# Mosfet_Driver.net
KiCad netlist of a schematic drawn in Altium Designer
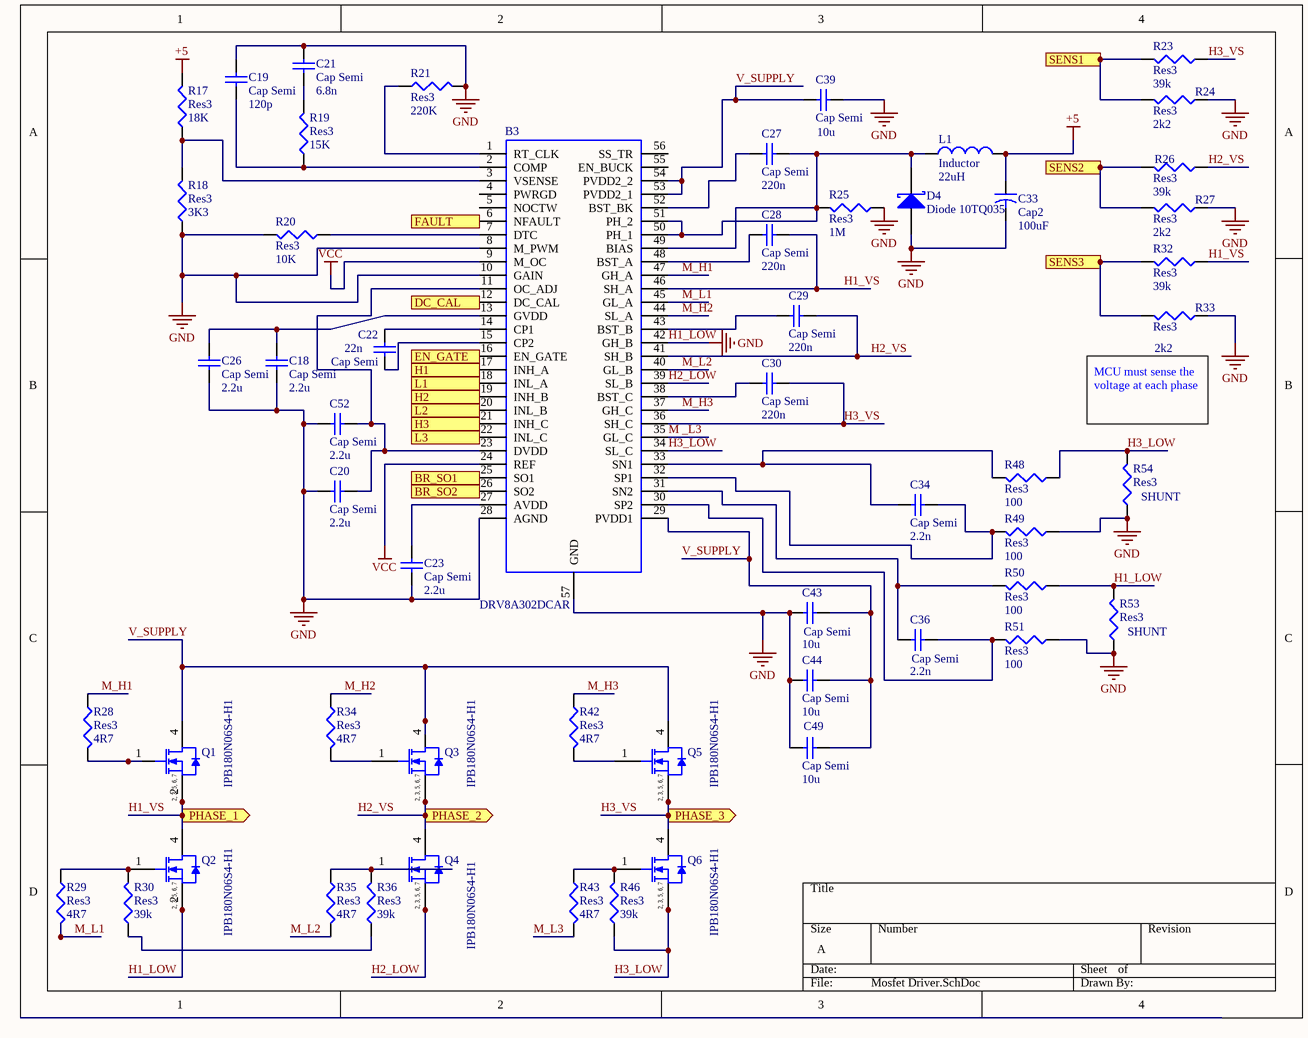
[diagram p0: Mosfet Driver.SchDoc]

(export (version "E")
  (design (tool "Eeschema 10.0.6"))
  (components
    (comp (ref "B3")
      (value "DRV8A302DCAR")
      (footprint "SOP50P810X120-57N")
      (description "3-Phase Brushless Motor Pre-Driver with Dual Current Sense Amps and Buck Converter (PWM Ctrl)")
      (fields (field (name "MANUFACTURER_PART_NUMBER") "DRV8302DCAR"))
      (libsource (lib "DRV8302DCAR") (part "DRV8302DCAR"))
    )
    (comp (ref "C18")
      (value "Cap Semi")
      (footprint "1608[0603]")
      (description "Capacitor (Semiconductor SIM Model)")
      (fields (field (name "ALTIUM_VALUE") "2.2u") (field (name "PUBLISHER") "Altium Limited"))
      (libsource (lib "Miscellaneous Devices") (part "Cap Semi"))
    )
    (comp (ref "C19")
      (value "Cap Semi")
      (footprint "1608[0603]")
      (description "Capacitor (Semiconductor SIM Model)")
      (fields (field (name "ALTIUM_VALUE") "120p") (field (name "PUBLISHER") "Altium Limited"))
      (libsource (lib "Miscellaneous Devices") (part "Cap Semi"))
    )
    (comp (ref "C20")
      (value "Cap Semi")
      (footprint "1608[0603]")
      (description "Capacitor (Semiconductor SIM Model)")
      (fields (field (name "ALTIUM_VALUE") "2.2u") (field (name "PUBLISHER") "Altium Limited"))
      (libsource (lib "Miscellaneous Devices") (part "Cap Semi"))
    )
    (comp (ref "C21")
      (value "Cap Semi")
      (footprint "1608[0603]")
      (description "Capacitor (Semiconductor SIM Model)")
      (fields (field (name "ALTIUM_VALUE") "6.8n") (field (name "PUBLISHER") "Altium Limited"))
      (libsource (lib "Miscellaneous Devices") (part "Cap Semi"))
    )
    (comp (ref "C22")
      (value "Cap Semi")
      (footprint "1608[0603]")
      (description "Capacitor (Semiconductor SIM Model)")
      (fields (field (name "ALTIUM_VALUE") "22n") (field (name "PUBLISHER") "Altium Limited"))
      (libsource (lib "Miscellaneous Devices") (part "Cap Semi"))
    )
    (comp (ref "C23")
      (value "Cap Semi")
      (footprint "1608[0603]")
      (description "Capacitor (Semiconductor SIM Model)")
      (fields (field (name "ALTIUM_VALUE") "2.2u") (field (name "PUBLISHER") "Altium Limited"))
      (libsource (lib "Miscellaneous Devices") (part "Cap Semi"))
    )
    (comp (ref "C26")
      (value "Cap Semi")
      (footprint "1608[0603]")
      (description "Capacitor (Semiconductor SIM Model)")
      (fields (field (name "ALTIUM_VALUE") "2.2u") (field (name "PUBLISHER") "Altium Limited"))
      (libsource (lib "Miscellaneous Devices") (part "Cap Semi"))
    )
    (comp (ref "C27")
      (value "Cap Semi")
      (footprint "1608[0603]")
      (description "Capacitor (Semiconductor SIM Model)")
      (fields (field (name "ALTIUM_VALUE") "220n") (field (name "PUBLISHER") "Altium Limited"))
      (libsource (lib "Miscellaneous Devices") (part "Cap Semi"))
    )
    (comp (ref "C28")
      (value "Cap Semi")
      (footprint "1608[0603]")
      (description "Capacitor (Semiconductor SIM Model)")
      (fields (field (name "ALTIUM_VALUE") "220n") (field (name "PUBLISHER") "Altium Limited"))
      (libsource (lib "Miscellaneous Devices") (part "Cap Semi"))
    )
    (comp (ref "C29")
      (value "Cap Semi")
      (footprint "1608[0603]")
      (description "Capacitor (Semiconductor SIM Model)")
      (fields (field (name "ALTIUM_VALUE") "220n") (field (name "PUBLISHER") "Altium Limited"))
      (libsource (lib "Miscellaneous Devices") (part "Cap Semi"))
    )
    (comp (ref "C30")
      (value "Cap Semi")
      (footprint "1608[0603]")
      (description "Capacitor (Semiconductor SIM Model)")
      (fields (field (name "ALTIUM_VALUE") "220n") (field (name "PUBLISHER") "Altium Limited"))
      (libsource (lib "Miscellaneous Devices") (part "Cap Semi"))
    )
    (comp (ref "C33")
      (value "Cap2")
      (footprint "CAPR5-4X5")
      (description "Capacitor")
      (fields (field (name "ALTIUM_VALUE") "100uF") (field (name "PUBLISHER") "Altium Limited"))
      (libsource (lib "Miscellaneous Devices") (part "Cap2"))
    )
    (comp (ref "C34")
      (value "Cap Semi")
      (footprint "1608[0603]")
      (description "Capacitor (Semiconductor SIM Model)")
      (fields (field (name "ALTIUM_VALUE") "2.2n") (field (name "PUBLISHER") "Altium Limited"))
      (libsource (lib "Miscellaneous Devices") (part "Cap Semi"))
    )
    (comp (ref "C36")
      (value "Cap Semi")
      (footprint "1608[0603]")
      (description "Capacitor (Semiconductor SIM Model)")
      (fields (field (name "ALTIUM_VALUE") "2.2n") (field (name "PUBLISHER") "Altium Limited"))
      (libsource (lib "Miscellaneous Devices") (part "Cap Semi"))
    )
    (comp (ref "C39")
      (value "Cap Semi")
      (footprint "1608[0603]")
      (description "Capacitor (Semiconductor SIM Model)")
      (fields (field (name "ALTIUM_VALUE") "10u") (field (name "PUBLISHER") "Altium Limited"))
      (libsource (lib "Miscellaneous Devices") (part "Cap Semi"))
    )
    (comp (ref "C43")
      (value "Cap Semi")
      (footprint "1608[0603]")
      (description "Capacitor (Semiconductor SIM Model)")
      (fields (field (name "ALTIUM_VALUE") "10u") (field (name "PUBLISHER") "Altium Limited"))
      (libsource (lib "Miscellaneous Devices") (part "Cap Semi"))
    )
    (comp (ref "C44")
      (value "Cap Semi")
      (footprint "1608[0603]")
      (description "Capacitor (Semiconductor SIM Model)")
      (fields (field (name "ALTIUM_VALUE") "10u") (field (name "PUBLISHER") "Altium Limited"))
      (libsource (lib "Miscellaneous Devices") (part "Cap Semi"))
    )
    (comp (ref "C49")
      (value "Cap Semi")
      (footprint "1608[0603]")
      (description "Capacitor (Semiconductor SIM Model)")
      (fields (field (name "ALTIUM_VALUE") "10u") (field (name "PUBLISHER") "Altium Limited"))
      (libsource (lib "Miscellaneous Devices") (part "Cap Semi"))
    )
    (comp (ref "C52")
      (value "Cap Semi")
      (footprint "1608[0603]")
      (description "Capacitor (Semiconductor SIM Model)")
      (fields (field (name "ALTIUM_VALUE") "2.2u") (field (name "PUBLISHER") "Altium Limited"))
      (libsource (lib "Miscellaneous Devices") (part "Cap Semi"))
    )
    (comp (ref "D4")
      (value "Diode 10TQ035")
      (footprint "TO-220AC")
      (description "Schottky Rectifier")
      (fields (field (name "PUBLISHER") "Altium Limited"))
      (libsource (lib "Miscellaneous Devices") (part "Diode 10TQ035"))
    )
    (comp (ref "L1")
      (value "Inductor")
      (footprint "0402-A")
      (fields (field (name "ALTIUM_VALUE") "22uH") (field (name "PUBLISHER") "Altium Limited"))
      (libsource (lib "Miscellaneous Devices") (part "Inductor"))
    )
    (comp (ref "Q1")
      (value "IPB180N06S4-H1")
      (footprint "INF-PG-TO263-7-3_N")
      (description "OptiMOS-T2 Power-Transistor, 60 V VDS, 180 A ID, PG-TO263-7-3, Reel, Green")
      (fields (field (name "MANUFACTURER") "Infineon"))
      (libsource (lib "Infineon_Power_MOSFET") (part "IPB180N06S4-H1"))
    )
    (comp (ref "Q2")
      (value "IPB180N06S4-H1")
      (footprint "INF-PG-TO263-7-3_N")
      (description "OptiMOS-T2 Power-Transistor, 60 V VDS, 180 A ID, PG-TO263-7-3, Reel, Green")
      (fields (field (name "MANUFACTURER") "Infineon"))
      (libsource (lib "Infineon_Power_MOSFET") (part "IPB180N06S4-H1"))
    )
    (comp (ref "Q3")
      (value "IPB180N06S4-H1")
      (footprint "INF-PG-TO263-7-3_N")
      (description "OptiMOS-T2 Power-Transistor, 60 V VDS, 180 A ID, PG-TO263-7-3, Reel, Green")
      (fields (field (name "MANUFACTURER") "Infineon"))
      (libsource (lib "Infineon_Power_MOSFET") (part "IPB180N06S4-H1"))
    )
    (comp (ref "Q4")
      (value "IPB180N06S4-H1")
      (footprint "INF-PG-TO263-7-3_N")
      (description "OptiMOS-T2 Power-Transistor, 60 V VDS, 180 A ID, PG-TO263-7-3, Reel, Green")
      (fields (field (name "MANUFACTURER") "Infineon"))
      (libsource (lib "Infineon_Power_MOSFET") (part "IPB180N06S4-H1"))
    )
    (comp (ref "Q5")
      (value "IPB180N06S4-H1")
      (footprint "INF-PG-TO263-7-3_N")
      (description "OptiMOS-T2 Power-Transistor, 60 V VDS, 180 A ID, PG-TO263-7-3, Reel, Green")
      (fields (field (name "MANUFACTURER") "Infineon"))
      (libsource (lib "Infineon_Power_MOSFET") (part "IPB180N06S4-H1"))
    )
    (comp (ref "Q6")
      (value "IPB180N06S4-H1")
      (footprint "INF-PG-TO263-7-3_N")
      (description "OptiMOS-T2 Power-Transistor, 60 V VDS, 180 A ID, PG-TO263-7-3, Reel, Green")
      (fields (field (name "MANUFACTURER") "Infineon"))
      (libsource (lib "Infineon_Power_MOSFET") (part "IPB180N06S4-H1"))
    )
    (comp (ref "R17")
      (value "Res3")
      (footprint "J1-0603")
      (description "Resistor")
      (fields (field (name "ALTIUM_VALUE") "18K") (field (name "PUBLISHER") "Altium Limited"))
      (libsource (lib "Miscellaneous Devices") (part "Res3"))
    )
    (comp (ref "R18")
      (value "Res3")
      (footprint "J1-0603")
      (description "Resistor")
      (fields (field (name "ALTIUM_VALUE") "3K3") (field (name "PUBLISHER") "Altium Limited"))
      (libsource (lib "Miscellaneous Devices") (part "Res3"))
    )
    (comp (ref "R19")
      (value "Res3")
      (footprint "J1-0603")
      (description "Resistor")
      (fields (field (name "ALTIUM_VALUE") "15K") (field (name "PUBLISHER") "Altium Limited"))
      (libsource (lib "Miscellaneous Devices") (part "Res3"))
    )
    (comp (ref "R20")
      (value "Res3")
      (footprint "J1-0603")
      (description "Resistor")
      (fields (field (name "ALTIUM_VALUE") "10K") (field (name "PUBLISHER") "Altium Limited"))
      (libsource (lib "Miscellaneous Devices") (part "Res3"))
    )
    (comp (ref "R21")
      (value "Res3")
      (footprint "J1-0603")
      (description "Resistor")
      (fields (field (name "ALTIUM_VALUE") "220K") (field (name "PUBLISHER") "Altium Limited"))
      (libsource (lib "Miscellaneous Devices") (part "Res3"))
    )
    (comp (ref "R23")
      (value "Res3")
      (footprint "J1-0603")
      (description "Resistor")
      (fields (field (name "ALTIUM_VALUE") "39k") (field (name "PUBLISHER") "Altium Limited"))
      (libsource (lib "Miscellaneous Devices") (part "Res3"))
    )
    (comp (ref "R24")
      (value "Res3")
      (footprint "J1-0603")
      (description "Resistor")
      (fields (field (name "ALTIUM_VALUE") "2k2") (field (name "PUBLISHER") "Altium Limited"))
      (libsource (lib "Miscellaneous Devices") (part "Res3"))
    )
    (comp (ref "R25")
      (value "Res3")
      (footprint "J1-0603")
      (description "Resistor")
      (fields (field (name "ALTIUM_VALUE") "1M") (field (name "PUBLISHER") "Altium Limited"))
      (libsource (lib "Miscellaneous Devices") (part "Res3"))
    )
    (comp (ref "R26")
      (value "Res3")
      (footprint "J1-0603")
      (description "Resistor")
      (fields (field (name "ALTIUM_VALUE") "39k") (field (name "PUBLISHER") "Altium Limited"))
      (libsource (lib "Miscellaneous Devices") (part "Res3"))
    )
    (comp (ref "R27")
      (value "Res3")
      (footprint "J1-0603")
      (description "Resistor")
      (fields (field (name "ALTIUM_VALUE") "2k2") (field (name "PUBLISHER") "Altium Limited"))
      (libsource (lib "Miscellaneous Devices") (part "Res3"))
    )
    (comp (ref "R28")
      (value "Res3")
      (footprint "J1-0603")
      (description "Resistor")
      (fields (field (name "ALTIUM_VALUE") "4R7") (field (name "PUBLISHER") "Altium Limited"))
      (libsource (lib "Miscellaneous Devices") (part "Res3"))
    )
    (comp (ref "R29")
      (value "Res3")
      (footprint "J1-0603")
      (description "Resistor")
      (fields (field (name "ALTIUM_VALUE") "4R7") (field (name "PUBLISHER") "Altium Limited"))
      (libsource (lib "Miscellaneous Devices") (part "Res3"))
    )
    (comp (ref "R30")
      (value "Res3")
      (footprint "J1-0603")
      (description "Resistor")
      (fields (field (name "ALTIUM_VALUE") "39k") (field (name "PUBLISHER") "Altium Limited"))
      (libsource (lib "Miscellaneous Devices") (part "Res3"))
    )
    (comp (ref "R32")
      (value "Res3")
      (footprint "J1-0603")
      (description "Resistor")
      (fields (field (name "ALTIUM_VALUE") "39k") (field (name "PUBLISHER") "Altium Limited"))
      (libsource (lib "Miscellaneous Devices") (part "Res3"))
    )
    (comp (ref "R33")
      (value "Res3")
      (footprint "J1-0603")
      (description "Resistor")
      (fields (field (name "ALTIUM_VALUE") "2k2") (field (name "PUBLISHER") "Altium Limited"))
      (libsource (lib "Miscellaneous Devices") (part "Res3"))
    )
    (comp (ref "R34")
      (value "Res3")
      (footprint "J1-0603")
      (description "Resistor")
      (fields (field (name "ALTIUM_VALUE") "4R7") (field (name "PUBLISHER") "Altium Limited"))
      (libsource (lib "Miscellaneous Devices") (part "Res3"))
    )
    (comp (ref "R35")
      (value "Res3")
      (footprint "J1-0603")
      (description "Resistor")
      (fields (field (name "ALTIUM_VALUE") "4R7") (field (name "PUBLISHER") "Altium Limited"))
      (libsource (lib "Miscellaneous Devices") (part "Res3"))
    )
    (comp (ref "R36")
      (value "Res3")
      (footprint "J1-0603")
      (description "Resistor")
      (fields (field (name "ALTIUM_VALUE") "39k") (field (name "PUBLISHER") "Altium Limited"))
      (libsource (lib "Miscellaneous Devices") (part "Res3"))
    )
    (comp (ref "R42")
      (value "Res3")
      (footprint "J1-0603")
      (description "Resistor")
      (fields (field (name "ALTIUM_VALUE") "4R7") (field (name "PUBLISHER") "Altium Limited"))
      (libsource (lib "Miscellaneous Devices") (part "Res3"))
    )
    (comp (ref "R43")
      (value "Res3")
      (footprint "J1-0603")
      (description "Resistor")
      (fields (field (name "ALTIUM_VALUE") "4R7") (field (name "PUBLISHER") "Altium Limited"))
      (libsource (lib "Miscellaneous Devices") (part "Res3"))
    )
    (comp (ref "R46")
      (value "Res3")
      (footprint "J1-0603")
      (description "Resistor")
      (fields (field (name "ALTIUM_VALUE") "39k") (field (name "PUBLISHER") "Altium Limited"))
      (libsource (lib "Miscellaneous Devices") (part "Res3"))
    )
    (comp (ref "R48")
      (value "Res3")
      (footprint "J1-0603")
      (description "Resistor")
      (fields (field (name "ALTIUM_VALUE") "100") (field (name "PUBLISHER") "Altium Limited"))
      (libsource (lib "Miscellaneous Devices") (part "Res3"))
    )
    (comp (ref "R49")
      (value "Res3")
      (footprint "J1-0603")
      (description "Resistor")
      (fields (field (name "ALTIUM_VALUE") "100") (field (name "PUBLISHER") "Altium Limited"))
      (libsource (lib "Miscellaneous Devices") (part "Res3"))
    )
    (comp (ref "R50")
      (value "Res3")
      (footprint "J1-0603")
      (description "Resistor")
      (fields (field (name "ALTIUM_VALUE") "100") (field (name "PUBLISHER") "Altium Limited"))
      (libsource (lib "Miscellaneous Devices") (part "Res3"))
    )
    (comp (ref "R51")
      (value "Res3")
      (footprint "J1-0603")
      (description "Resistor")
      (fields (field (name "ALTIUM_VALUE") "100") (field (name "PUBLISHER") "Altium Limited"))
      (libsource (lib "Miscellaneous Devices") (part "Res3"))
    )
    (comp (ref "R53")
      (value "Res3")
      (footprint "J1-0603")
      (description "Resistor")
      (fields (field (name "ALTIUM_VALUE") "SHUNT") (field (name "PUBLISHER") "Altium Limited"))
      (libsource (lib "Miscellaneous Devices") (part "Res3"))
    )
    (comp (ref "R54")
      (value "Res3")
      (footprint "J1-0603")
      (description "Resistor")
      (fields (field (name "ALTIUM_VALUE") "SHUNT") (field (name "PUBLISHER") "Altium Limited"))
      (libsource (lib "Miscellaneous Devices") (part "Res3"))
    )
  )
  (nets
    (net (code "1") (name "+5") (class "Default")
      (node (ref "C33") (pin "1") (pinfunction "1_1") (pintype "passive"))
      (node (ref "L1") (pin "2") (pinfunction "2_2") (pintype "passive"))
      (node (ref "R17") (pin "2") (pinfunction "2_2") (pintype "passive"))
    )
    (net (code "2") (name "/BR_SO1") (class "Default")
      (node (ref "B3") (pin "25") (pinfunction "SO1_25") (pintype "passive"))
    )
    (net (code "3") (name "/BR_SO2") (class "Default")
      (node (ref "B3") (pin "26") (pinfunction "SO2_26") (pintype "passive"))
    )
    (net (code "4") (name "/DC_CAL") (class "Default")
      (node (ref "B3") (pin "12") (pinfunction "DC_CAL_12") (pintype "passive"))
    )
    (net (code "5") (name "/EN_GATE") (class "Default")
      (node (ref "B3") (pin "16") (pinfunction "EN_GATE_16") (pintype "passive"))
    )
    (net (code "6") (name "/FAULT") (class "Default")
      (node (ref "B3") (pin "6") (pinfunction "NFAULT_6") (pintype "passive"))
    )
    (net (code "7") (name "/H1") (class "Default")
      (node (ref "B3") (pin "17") (pinfunction "INH_A_17") (pintype "passive"))
    )
    (net (code "8") (name "/H1_VS") (class "Default")
      (node (ref "B3") (pin "46") (pinfunction "SH_A_46") (pintype "passive"))
      (node (ref "C28") (pin "1") (pinfunction "1_1") (pintype "passive"))
      (node (ref "Q1") (pin "2") (pinfunction "SOURCE_2") (pintype "passive"))
      (node (ref "Q1") (pin "3") (pinfunction "SOURCE_3") (pintype "passive"))
      (node (ref "Q1") (pin "5") (pinfunction "SOURCE_5") (pintype "passive"))
      (node (ref "Q1") (pin "6") (pinfunction "SOURCE_6") (pintype "passive"))
      (node (ref "Q1") (pin "7") (pinfunction "SOURCE_7") (pintype "passive"))
      (node (ref "Q2") (pin "4") (pinfunction "DRAIN_4") (pintype "passive"))
      (node (ref "R32") (pin "1") (pinfunction "1_1") (pintype "passive"))
    )
    (net (code "9") (name "/H2") (class "Default")
      (node (ref "B3") (pin "19") (pinfunction "INH_B_19") (pintype "passive"))
    )
    (net (code "10") (name "/H2_LOW") (class "Default")
      (node (ref "B3") (pin "39") (pinfunction "SL_B_39") (pintype "passive"))
      (node (ref "Q4") (pin "2") (pinfunction "SOURCE_2") (pintype "passive"))
      (node (ref "Q4") (pin "3") (pinfunction "SOURCE_3") (pintype "passive"))
      (node (ref "Q4") (pin "5") (pinfunction "SOURCE_5") (pintype "passive"))
      (node (ref "Q4") (pin "6") (pinfunction "SOURCE_6") (pintype "passive"))
      (node (ref "Q4") (pin "7") (pinfunction "SOURCE_7") (pintype "passive"))
    )
    (net (code "11") (name "/H2_VS") (class "Default")
      (node (ref "B3") (pin "41") (pinfunction "SH_B_41") (pintype "passive"))
      (node (ref "C29") (pin "1") (pinfunction "1_1") (pintype "passive"))
      (node (ref "Q3") (pin "2") (pinfunction "SOURCE_2") (pintype "passive"))
      (node (ref "Q3") (pin "3") (pinfunction "SOURCE_3") (pintype "passive"))
      (node (ref "Q3") (pin "5") (pinfunction "SOURCE_5") (pintype "passive"))
      (node (ref "Q3") (pin "6") (pinfunction "SOURCE_6") (pintype "passive"))
      (node (ref "Q3") (pin "7") (pinfunction "SOURCE_7") (pintype "passive"))
      (node (ref "Q4") (pin "4") (pinfunction "DRAIN_4") (pintype "passive"))
      (node (ref "R26") (pin "1") (pinfunction "1_1") (pintype "passive"))
    )
    (net (code "12") (name "/H3") (class "Default")
      (node (ref "B3") (pin "21") (pinfunction "INH_C_21") (pintype "passive"))
    )
    (net (code "13") (name "/H3_LOW") (class "Default")
      (node (ref "B3") (pin "34") (pinfunction "SL_C_34") (pintype "passive"))
      (node (ref "Q6") (pin "2") (pinfunction "SOURCE_2") (pintype "passive"))
      (node (ref "Q6") (pin "3") (pinfunction "SOURCE_3") (pintype "passive"))
      (node (ref "Q6") (pin "5") (pinfunction "SOURCE_5") (pintype "passive"))
      (node (ref "Q6") (pin "6") (pinfunction "SOURCE_6") (pintype "passive"))
      (node (ref "Q6") (pin "7") (pinfunction "SOURCE_7") (pintype "passive"))
      (node (ref "R46") (pin "1") (pinfunction "1_1") (pintype "passive"))
      (node (ref "R48") (pin "1") (pinfunction "1_1") (pintype "passive"))
      (node (ref "R54") (pin "2") (pinfunction "2_2") (pintype "passive"))
    )
    (net (code "14") (name "/H3_VS") (class "Default")
      (node (ref "B3") (pin "36") (pinfunction "SH_C_36") (pintype "passive"))
      (node (ref "C30") (pin "1") (pinfunction "1_1") (pintype "passive"))
      (node (ref "Q5") (pin "2") (pinfunction "SOURCE_2") (pintype "passive"))
      (node (ref "Q5") (pin "3") (pinfunction "SOURCE_3") (pintype "passive"))
      (node (ref "Q5") (pin "5") (pinfunction "SOURCE_5") (pintype "passive"))
      (node (ref "Q5") (pin "6") (pinfunction "SOURCE_6") (pintype "passive"))
      (node (ref "Q5") (pin "7") (pinfunction "SOURCE_7") (pintype "passive"))
      (node (ref "Q6") (pin "4") (pinfunction "DRAIN_4") (pintype "passive"))
      (node (ref "R23") (pin "1") (pinfunction "1_1") (pintype "passive"))
    )
    (net (code "15") (name "/L1") (class "Default")
      (node (ref "B3") (pin "18") (pinfunction "INL_A_18") (pintype "passive"))
    )
    (net (code "16") (name "/L2") (class "Default")
      (node (ref "B3") (pin "20") (pinfunction "INL_B_20") (pintype "passive"))
    )
    (net (code "17") (name "/L3") (class "Default")
      (node (ref "B3") (pin "22") (pinfunction "INL_C_22") (pintype "passive"))
    )
    (net (code "18") (name "/M _L3") (class "Default")
      (node (ref "B3") (pin "35") (pinfunction "GL_C_35") (pintype "passive"))
    )
    (net (code "19") (name "/M_H1") (class "Default")
      (node (ref "B3") (pin "47") (pinfunction "GH_A_47") (pintype "passive"))
      (node (ref "R28") (pin "1") (pinfunction "1_1") (pintype "passive"))
    )
    (net (code "20") (name "/M_H2") (class "Default")
      (node (ref "B3") (pin "44") (pinfunction "SL_A_44") (pintype "passive"))
      (node (ref "R34") (pin "1") (pinfunction "1_1") (pintype "passive"))
    )
    (net (code "21") (name "/M_H3") (class "Default")
      (node (ref "B3") (pin "37") (pinfunction "GH_C_37") (pintype "passive"))
      (node (ref "R42") (pin "1") (pinfunction "1_1") (pintype "passive"))
    )
    (net (code "22") (name "/M_L1") (class "Default")
      (node (ref "B3") (pin "45") (pinfunction "GL_A_45") (pintype "passive"))
      (node (ref "R29") (pin "2") (pinfunction "2_2") (pintype "passive"))
    )
    (net (code "23") (name "/M_L2") (class "Default")
      (node (ref "B3") (pin "40") (pinfunction "GL_B_40") (pintype "passive"))
      (node (ref "R35") (pin "2") (pinfunction "2_2") (pintype "passive"))
    )
    (net (code "24") (name "/M_L3") (class "Default")
      (node (ref "R43") (pin "2") (pinfunction "2_2") (pintype "passive"))
    )
    (net (code "25") (name "/SENS1") (class "Default")
      (node (ref "R23") (pin "2") (pinfunction "2_2") (pintype "passive"))
      (node (ref "R24") (pin "2") (pinfunction "2_2") (pintype "passive"))
    )
    (net (code "26") (name "/SENS2") (class "Default")
      (node (ref "R26") (pin "2") (pinfunction "2_2") (pintype "passive"))
      (node (ref "R27") (pin "2") (pinfunction "2_2") (pintype "passive"))
    )
    (net (code "27") (name "/SENS3") (class "Default")
      (node (ref "R32") (pin "2") (pinfunction "2_2") (pintype "passive"))
      (node (ref "R33") (pin "2") (pinfunction "2_2") (pintype "passive"))
    )
    (net (code "28") (name "/V_SUPPLY") (class "Default")
      (node (ref "B3") (pin "29") (pinfunction "PVDD1_29") (pintype "passive"))
      (node (ref "B3") (pin "53") (pinfunction "PVDD2_1_53") (pintype "passive"))
      (node (ref "B3") (pin "54") (pinfunction "PVDD2_2_54") (pintype "passive"))
      (node (ref "C39") (pin "2") (pinfunction "2_2") (pintype "passive"))
      (node (ref "C43") (pin "1") (pinfunction "1_1") (pintype "passive"))
      (node (ref "C44") (pin "1") (pinfunction "1_1") (pintype "passive"))
      (node (ref "C49") (pin "1") (pinfunction "1_1") (pintype "passive"))
      (node (ref "Q1") (pin "4") (pinfunction "DRAIN_4") (pintype "passive"))
      (node (ref "Q3") (pin "4") (pinfunction "DRAIN_4") (pintype "passive"))
      (node (ref "Q5") (pin "4") (pinfunction "DRAIN_4") (pintype "passive"))
    )
    (net (code "29") (name "GND") (class "Default")
      (node (ref "B3") (pin "10") (pinfunction "GAIN_10") (pintype "passive"))
      (node (ref "B3") (pin "28") (pinfunction "AGND_28") (pintype "passive"))
      (node (ref "B3") (pin "42") (pinfunction "GH_B_42") (pintype "passive"))
      (node (ref "B3") (pin "57") (pinfunction "GND_57") (pintype "passive"))
      (node (ref "B3") (pin "8") (pinfunction "M_PWM_8") (pintype "passive"))
      (node (ref "C18") (pin "1") (pinfunction "1_1") (pintype "passive"))
      (node (ref "C19") (pin "2") (pinfunction "2_2") (pintype "passive"))
      (node (ref "C20") (pin "2") (pinfunction "2_2") (pintype "passive"))
      (node (ref "C21") (pin "2") (pinfunction "2_2") (pintype "passive"))
      (node (ref "C23") (pin "2") (pinfunction "2_2") (pintype "passive"))
      (node (ref "C26") (pin "1") (pinfunction "1_1") (pintype "passive"))
      (node (ref "C33") (pin "2") (pinfunction "2_2") (pintype "passive"))
      (node (ref "C39") (pin "1") (pinfunction "1_1") (pintype "passive"))
      (node (ref "C43") (pin "2") (pinfunction "2_2") (pintype "passive"))
      (node (ref "C44") (pin "2") (pinfunction "2_2") (pintype "passive"))
      (node (ref "C49") (pin "2") (pinfunction "2_2") (pintype "passive"))
      (node (ref "C52") (pin "2") (pinfunction "2_2") (pintype "passive"))
      (node (ref "D4") (pin "3") (pinfunction "A_3") (pintype "passive"))
      (node (ref "Q2") (pin "2") (pinfunction "SOURCE_2") (pintype "passive"))
      (node (ref "Q2") (pin "3") (pinfunction "SOURCE_3") (pintype "passive"))
      (node (ref "Q2") (pin "5") (pinfunction "SOURCE_5") (pintype "passive"))
      (node (ref "Q2") (pin "6") (pinfunction "SOURCE_6") (pintype "passive"))
      (node (ref "Q2") (pin "7") (pinfunction "SOURCE_7") (pintype "passive"))
      (node (ref "R18") (pin "1") (pinfunction "1_1") (pintype "passive"))
      (node (ref "R20") (pin "2") (pinfunction "2_2") (pintype "passive"))
      (node (ref "R21") (pin "2") (pinfunction "2_2") (pintype "passive"))
      (node (ref "R24") (pin "1") (pinfunction "1_1") (pintype "passive"))
      (node (ref "R25") (pin "1") (pinfunction "1_1") (pintype "passive"))
      (node (ref "R27") (pin "1") (pinfunction "1_1") (pintype "passive"))
      (node (ref "R33") (pin "1") (pinfunction "1_1") (pintype "passive"))
      (node (ref "R49") (pin "1") (pinfunction "1_1") (pintype "passive"))
      (node (ref "R50") (pin "1") (pinfunction "1_1") (pintype "passive"))
      (node (ref "R51") (pin "1") (pinfunction "1_1") (pintype "passive"))
      (node (ref "R53") (pin "1") (pinfunction "1_1") (pintype "passive"))
      (node (ref "R53") (pin "2") (pinfunction "2_2") (pintype "passive"))
      (node (ref "R54") (pin "1") (pinfunction "1_1") (pintype "passive"))
    )
    (net (code "30") (name "Net-(B3-AVDD)") (class "Default")
      (node (ref "B3") (pin "27") (pinfunction "AVDD_27") (pintype "passive"))
      (node (ref "C23") (pin "1") (pinfunction "1_1") (pintype "passive"))
    )
    (net (code "31") (name "Net-(B3-BIAS)") (class "Default")
      (node (ref "B3") (pin "49") (pinfunction "BIAS_49") (pintype "passive"))
      (node (ref "B3") (pin "50") (pinfunction "PH_1_50") (pintype "passive"))
      (node (ref "B3") (pin "51") (pinfunction "PH_2_51") (pintype "passive"))
      (node (ref "C27") (pin "1") (pinfunction "1_1") (pintype "passive"))
      (node (ref "D4") (pin "1") (pinfunction "K_1") (pintype "passive"))
      (node (ref "L1") (pin "1") (pinfunction "1_1") (pintype "passive"))
      (node (ref "R25") (pin "2") (pinfunction "2_2") (pintype "passive"))
    )
    (net (code "32") (name "Net-(B3-BST_A)") (class "Default")
      (node (ref "B3") (pin "48") (pinfunction "BST_A_48") (pintype "passive"))
      (node (ref "C28") (pin "2") (pinfunction "2_2") (pintype "passive"))
    )
    (net (code "33") (name "Net-(B3-BST_B)") (class "Default")
      (node (ref "B3") (pin "43") (pinfunction "BST_B_43") (pintype "passive"))
      (node (ref "C29") (pin "2") (pinfunction "2_2") (pintype "passive"))
    )
    (net (code "34") (name "Net-(B3-BST_BK)") (class "Default")
      (node (ref "B3") (pin "52") (pinfunction "BST_BK_52") (pintype "passive"))
      (node (ref "C27") (pin "2") (pinfunction "2_2") (pintype "passive"))
    )
    (net (code "35") (name "Net-(B3-BST_C)") (class "Default")
      (node (ref "B3") (pin "38") (pinfunction "BST_C_38") (pintype "passive"))
      (node (ref "C30") (pin "2") (pinfunction "2_2") (pintype "passive"))
    )
    (net (code "36") (name "Net-(B3-COMP)") (class "Default")
      (node (ref "B3") (pin "2") (pinfunction "COMP_2") (pintype "passive"))
      (node (ref "C19") (pin "1") (pinfunction "1_1") (pintype "passive"))
      (node (ref "R19") (pin "1") (pinfunction "1_1") (pintype "passive"))
    )
    (net (code "37") (name "Net-(B3-CP1)") (class "Default")
      (node (ref "B3") (pin "14") (pinfunction "CP1_14") (pintype "passive"))
      (node (ref "C22") (pin "1") (pinfunction "1_1") (pintype "passive"))
    )
    (net (code "38") (name "Net-(B3-CP2)") (class "Default")
      (node (ref "B3") (pin "15") (pinfunction "CP2_15") (pintype "passive"))
      (node (ref "C22") (pin "2") (pinfunction "2_2") (pintype "passive"))
    )
    (net (code "39") (name "Net-(B3-DTC)") (class "Default")
      (node (ref "B3") (pin "7") (pinfunction "DTC_7") (pintype "passive"))
      (node (ref "R20") (pin "1") (pinfunction "1_1") (pintype "passive"))
    )
    (net (code "40") (name "Net-(B3-DVDD)") (class "Default")
      (node (ref "B3") (pin "11") (pinfunction "OC_ADJ_11") (pintype "passive"))
      (node (ref "B3") (pin "23") (pinfunction "DVDD_23") (pintype "passive"))
      (node (ref "C20") (pin "1") (pinfunction "1_1") (pintype "passive"))
      (node (ref "C52") (pin "1") (pinfunction "1_1") (pintype "passive"))
    )
    (net (code "41") (name "Net-(B3-GVDD)") (class "Default")
      (node (ref "B3") (pin "13") (pinfunction "GVDD_13") (pintype "passive"))
      (node (ref "C18") (pin "2") (pinfunction "2_2") (pintype "passive"))
      (node (ref "C26") (pin "2") (pinfunction "2_2") (pintype "passive"))
    )
    (net (code "42") (name "Net-(B3-RT_CLK)") (class "Default")
      (node (ref "B3") (pin "1") (pinfunction "RT_CLK_1") (pintype "passive"))
      (node (ref "R21") (pin "1") (pinfunction "1_1") (pintype "passive"))
    )
    (net (code "43") (name "Net-(B3-SN1)") (class "Default")
      (node (ref "B3") (pin "33") (pinfunction "SN1_33") (pintype "passive"))
      (node (ref "C34") (pin "2") (pinfunction "2_2") (pintype "passive"))
      (node (ref "R48") (pin "2") (pinfunction "2_2") (pintype "passive"))
    )
    (net (code "44") (name "Net-(B3-SN2)") (class "Default")
      (node (ref "B3") (pin "31") (pinfunction "SN2_31") (pintype "passive"))
      (node (ref "C36") (pin "2") (pinfunction "2_2") (pintype "passive"))
      (node (ref "R50") (pin "2") (pinfunction "2_2") (pintype "passive"))
    )
    (net (code "45") (name "Net-(B3-SP1)") (class "Default")
      (node (ref "B3") (pin "32") (pinfunction "SP1_32") (pintype "passive"))
      (node (ref "C34") (pin "1") (pinfunction "1_1") (pintype "passive"))
      (node (ref "R49") (pin "2") (pinfunction "2_2") (pintype "passive"))
    )
    (net (code "46") (name "Net-(B3-SP2)") (class "Default")
      (node (ref "B3") (pin "30") (pinfunction "SP2_30") (pintype "passive"))
      (node (ref "C36") (pin "1") (pinfunction "1_1") (pintype "passive"))
      (node (ref "R51") (pin "2") (pinfunction "2_2") (pintype "passive"))
    )
    (net (code "47") (name "Net-(B3-VSENSE)") (class "Default")
      (node (ref "B3") (pin "3") (pinfunction "VSENSE_3") (pintype "passive"))
      (node (ref "R17") (pin "1") (pinfunction "1_1") (pintype "passive"))
      (node (ref "R18") (pin "2") (pinfunction "2_2") (pintype "passive"))
    )
    (net (code "48") (name "Net-(C21-Pad1)") (class "Default")
      (node (ref "C21") (pin "1") (pinfunction "1_1") (pintype "passive"))
      (node (ref "R19") (pin "2") (pinfunction "2_2") (pintype "passive"))
    )
    (net (code "49") (name "Net-(Q1-GATE)") (class "Default")
      (node (ref "Q1") (pin "1") (pinfunction "GATE_1") (pintype "passive"))
      (node (ref "R28") (pin "2") (pinfunction "2_2") (pintype "passive"))
    )
    (net (code "50") (name "Net-(Q2-GATE)") (class "Default")
      (node (ref "Q2") (pin "1") (pinfunction "GATE_1") (pintype "passive"))
      (node (ref "R29") (pin "1") (pinfunction "1_1") (pintype "passive"))
      (node (ref "R30") (pin "2") (pinfunction "2_2") (pintype "passive"))
    )
    (net (code "51") (name "Net-(Q3-GATE)") (class "Default")
      (node (ref "Q3") (pin "1") (pinfunction "GATE_1") (pintype "passive"))
      (node (ref "R34") (pin "2") (pinfunction "2_2") (pintype "passive"))
    )
    (net (code "52") (name "Net-(Q4-GATE)") (class "Default")
      (node (ref "Q4") (pin "1") (pinfunction "GATE_1") (pintype "passive"))
      (node (ref "R35") (pin "1") (pinfunction "1_1") (pintype "passive"))
      (node (ref "R36") (pin "2") (pinfunction "2_2") (pintype "passive"))
    )
    (net (code "53") (name "Net-(Q5-GATE)") (class "Default")
      (node (ref "Q5") (pin "1") (pinfunction "GATE_1") (pintype "passive"))
      (node (ref "R42") (pin "2") (pinfunction "2_2") (pintype "passive"))
    )
    (net (code "54") (name "Net-(Q6-GATE)") (class "Default")
      (node (ref "Q6") (pin "1") (pinfunction "GATE_1") (pintype "passive"))
      (node (ref "R43") (pin "1") (pinfunction "1_1") (pintype "passive"))
      (node (ref "R46") (pin "2") (pinfunction "2_2") (pintype "passive"))
    )
    (net (code "55") (name "Net-(R30-Pad1)") (class "Default")
      (node (ref "R30") (pin "1") (pinfunction "1_1") (pintype "passive"))
      (node (ref "R36") (pin "1") (pinfunction "1_1") (pintype "passive"))
    )
    (net (code "56") (name "VCC") (class "Default")
      (node (ref "B3") (pin "24") (pinfunction "REF_24") (pintype "passive"))
      (node (ref "B3") (pin "9") (pinfunction "M_OC_9") (pintype "passive"))
    )
    (net (code "57") (name "unconnected-(B3-EN_BUCK-Pad55)") (class "Default")
      (node (ref "B3") (pin "55") (pinfunction "EN_BUCK_55") (pintype "passive"))
    )
    (net (code "58") (name "unconnected-(B3-NOCTW-Pad5)") (class "Default")
      (node (ref "B3") (pin "5") (pinfunction "NOCTW_5") (pintype "passive"))
    )
    (net (code "59") (name "unconnected-(B3-PWRGD-Pad4)") (class "Default")
      (node (ref "B3") (pin "4") (pinfunction "PWRGD_4") (pintype "passive"))
    )
    (net (code "60") (name "unconnected-(B3-SS_TR-Pad56)") (class "Default")
      (node (ref "B3") (pin "56") (pinfunction "SS_TR_56") (pintype "passive"))
    )
  )
)
